# power.net
KiCad netlist of a schematic drawn in Altium Designer
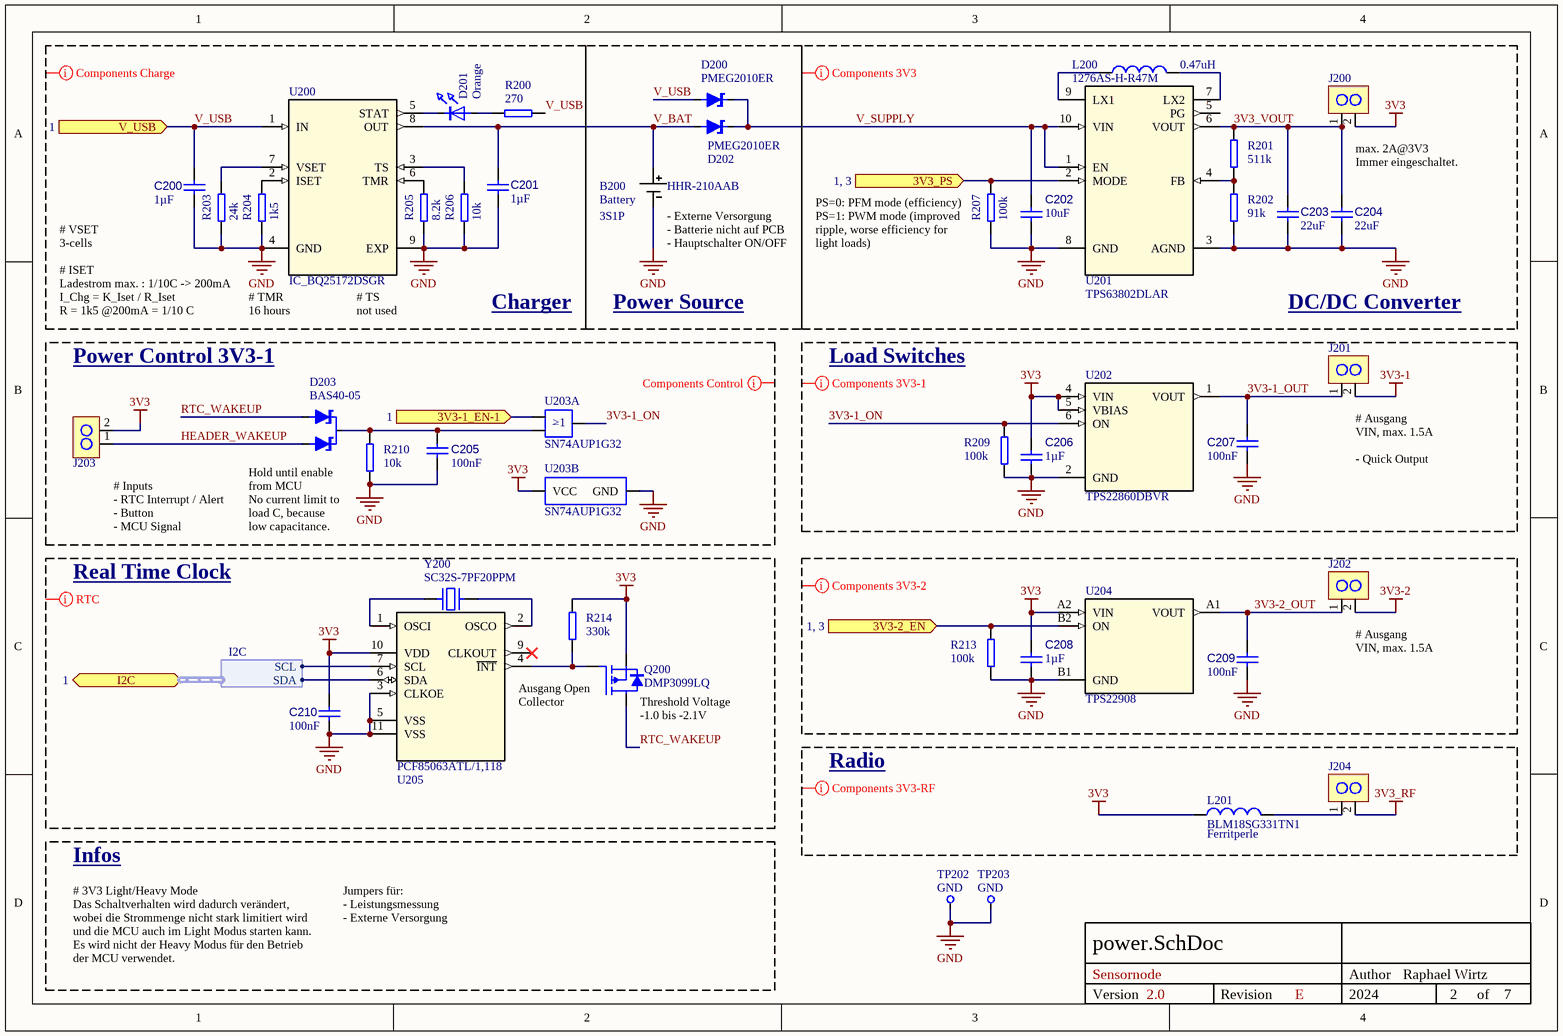
[diagram p0: power.SchDoc]

(export (version "E")
  (design (tool "Eeschema 10.0.6"))
  (components
    (comp (ref "B200")
      (value "Battery")
      (footprint "sensornode:JST-S2B-PH-K-S_V - Cloned")
      (fields (field (name "BATTERY_CONFIG") "3S1P") (field (name "PRODUCT") "HHR-210AAB"))
      (libsource (lib "sensornode_v2") (part "Battery"))
    )
    (comp (ref "C200")
      (value "1µF")
      (footprint "0402")
      (fields
        (field (name "TOLERANCE") "10%")
        (field (name "MANUFACTURER") "TDK")
        (field (name "MANUFACTURER PART NUMBER") "C1005X6S0J105K050BC")
      )
      (libsource (lib "sensornode_v2") (part "C"))
    )
    (comp (ref "C201")
      (value "1µF")
      (footprint "0402")
      (fields
        (field (name "TOLERANCE") "10%")
        (field (name "MANUFACTURER") "TDK")
        (field (name "MANUFACTURER PART NUMBER") "C1005X6S0J105K050BC")
      )
      (libsource (lib "sensornode_v2") (part "C"))
    )
    (comp (ref "C202")
      (value "10uF")
      (footprint "sensornode:0603")
      (fields
        (field (name "TOLERANCE") "10%")
        (field (name "MANUFACTURER") "TDK")
        (field (name "MANUFACTURER PART NUMBER") "C1005X6S0J105K050BC")
      )
      (libsource (lib "sensornode_v2") (part "C"))
    )
    (comp (ref "C203")
      (value "22uF")
      (footprint "sensornode:0603")
      (fields
        (field (name "TOLERANCE") "10%")
        (field (name "MANUFACTURER") "TDK")
        (field (name "MANUFACTURER PART NUMBER") "C1005X6S0J105K050BC")
      )
      (libsource (lib "sensornode_v2") (part "C"))
    )
    (comp (ref "C204")
      (value "22uF")
      (footprint "sensornode:0603")
      (fields
        (field (name "TOLERANCE") "10%")
        (field (name "MANUFACTURER") "TDK")
        (field (name "MANUFACTURER PART NUMBER") "C1005X6S0J105K050BC")
      )
      (libsource (lib "sensornode_v2") (part "C"))
    )
    (comp (ref "C205")
      (value "100nF")
      (footprint "sensornode:0603")
      (fields
        (field (name "TOLERANCE") "10%")
        (field (name "MANUFACTURER") "TDK")
        (field (name "MANUFACTURER PART NUMBER") "C1005X6S0J105K050BC")
      )
      (libsource (lib "sensornode_v2") (part "C"))
    )
    (comp (ref "C206")
      (value "1µF")
      (footprint "sensornode:0603")
      (fields
        (field (name "TOLERANCE") "10%")
        (field (name "MANUFACTURER") "TDK")
        (field (name "MANUFACTURER PART NUMBER") "C1005X6S0J105K050BC")
      )
      (libsource (lib "sensornode_v2") (part "C"))
    )
    (comp (ref "C207")
      (value "100nF")
      (footprint "sensornode:0603")
      (fields
        (field (name "TOLERANCE") "10%")
        (field (name "MANUFACTURER") "TDK")
        (field (name "MANUFACTURER PART NUMBER") "C1005X6S0J105K050BC")
      )
      (libsource (lib "sensornode_v2") (part "C"))
    )
    (comp (ref "C208")
      (value "1µF")
      (footprint "sensornode:0603")
      (fields
        (field (name "TOLERANCE") "10%")
        (field (name "MANUFACTURER") "TDK")
        (field (name "MANUFACTURER PART NUMBER") "C1005X6S0J105K050BC")
      )
      (libsource (lib "sensornode_v2") (part "C"))
    )
    (comp (ref "C209")
      (value "100nF")
      (footprint "sensornode:0603")
      (fields
        (field (name "TOLERANCE") "10%")
        (field (name "MANUFACTURER") "TDK")
        (field (name "MANUFACTURER PART NUMBER") "C1005X6S0J105K050BC")
      )
      (libsource (lib "sensornode_v2") (part "C"))
    )
    (comp (ref "C210")
      (value "100nF")
      (footprint "0402")
      (fields
        (field (name "TOLERANCE") "10%")
        (field (name "MANUFACTURER") "TDK")
        (field (name "MANUFACTURER PART NUMBER") "C1005X6S0J105K050BC")
      )
      (libsource (lib "sensornode_v2") (part "C"))
    )
    (comp (ref "D200")
      (value "PMEG2010ER")
      (footprint "sensornode:SODFL3517X110N")
      (libsource (lib "sensornode_v2") (part "Schotky_1"))
    )
    (comp (ref "D201")
      (value "Orange")
      (footprint "sensornode:0603-Diode")
      (libsource (lib "sensornode_v2") (part "LED_1"))
    )
    (comp (ref "D202")
      (value "PMEG2010ER")
      (footprint "sensornode:SODFL3517X110N")
      (libsource (lib "sensornode_v2") (part "Schotky_1"))
    )
    (comp (ref "D203")
      (value "BAS40-05")
      (footprint "sensornode:SOT-23")
      (libsource (lib "sensornode_v2") (part "Schotky_BAS40-5"))
    )
    (comp (ref "J200")
      (value "HEADER_2x1_TD")
      (footprint "sensornode:HEADER_2_RM_2.54")
      (libsource (lib "sensornode_v2") (part "HEADER_2x1_TD"))
    )
    (comp (ref "J201")
      (value "HEADER_2x1_TD")
      (footprint "sensornode:HEADER_2_RM_2.54")
      (libsource (lib "sensornode_v2") (part "HEADER_2x1_TD"))
    )
    (comp (ref "J202")
      (value "HEADER_2x1_TD")
      (footprint "sensornode:HEADER_2_RM_2.54")
      (libsource (lib "sensornode_v2") (part "HEADER_2x1_TD"))
    )
    (comp (ref "J203")
      (value "HEADER_2x1_TD")
      (footprint "sensornode:HEADER_2_RM_2.54")
      (libsource (lib "") (part "HEADER_2x1_TD_1"))
    )
    (comp (ref "J204")
      (value "HEADER_2x1_TD")
      (footprint "sensornode:HEADER_2_RM_2.54")
      (libsource (lib "sensornode_v2") (part "HEADER_2x1_TD"))
    )
    (comp (ref "L200")
      (value "0.47uH")
      (footprint "sensornode:FP-XFL4015-MFG")
      (fields (field (name "NAME") "1276AS-H-R47M"))
      (libsource (lib "sensornode_v2") (part "L?"))
    )
    (comp (ref "L201")
      (value "BLM18SG331TN1")
      (footprint "sensornode:1608X65N_BEADC")
      (description "330 Ohms @ 100 MHz 1 Power Line Ferrite Bead 0603 (1608 Metric) 1.5A 70mOhm")
      (fields (field (name "INFO") "Ferritperle"))
      (libsource (lib "sensornode_v2") (part "L?"))
    )
    (comp (ref "Q200")
      (value "DMP3099LQ")
      (footprint "SOT-23 - FET")
      (libsource (lib "AMZ_Altium_Lib") (part "MOSFET P"))
    )
    (comp (ref "R200")
      (value "270")
      (footprint "sensornode:0603")
      (description "Normaler Widerstand")
      (libsource (lib "sensornode_v2") (part "R?"))
    )
    (comp (ref "R201")
      (value "511k")
      (footprint "sensornode:0603")
      (description "Normaler Widerstand")
      (libsource (lib "sensornode_v2") (part "R?"))
    )
    (comp (ref "R202")
      (value "91k")
      (footprint "sensornode:0603")
      (description "Normaler Widerstand")
      (libsource (lib "sensornode_v2") (part "R?"))
    )
    (comp (ref "R203")
      (value "24k")
      (footprint "sensornode:0603")
      (description "Normaler Widerstand")
      (libsource (lib "sensornode_v2") (part "R?"))
    )
    (comp (ref "R204")
      (value "1k5")
      (footprint "sensornode:0603")
      (description "Normaler Widerstand")
      (libsource (lib "sensornode_v2") (part "R?"))
    )
    (comp (ref "R205")
      (value "8.2k")
      (footprint "sensornode:0603")
      (description "Normaler Widerstand")
      (libsource (lib "sensornode_v2") (part "R?"))
    )
    (comp (ref "R206")
      (value "10k")
      (footprint "sensornode:0603")
      (description "Normaler Widerstand")
      (libsource (lib "sensornode_v2") (part "R?"))
    )
    (comp (ref "R207")
      (value "100k")
      (footprint "sensornode:0603")
      (description "Normaler Widerstand")
      (libsource (lib "sensornode_v2") (part "R?"))
    )
    (comp (ref "R209")
      (value "100k")
      (footprint "sensornode:0603")
      (description "Normaler Widerstand")
      (libsource (lib "sensornode_v2") (part "R?"))
    )
    (comp (ref "R210")
      (value "10k")
      (footprint "sensornode:0603")
      (description "Normaler Widerstand")
      (libsource (lib "sensornode_v2") (part "R?"))
    )
    (comp (ref "R213")
      (value "100k")
      (footprint "sensornode:0603")
      (description "Normaler Widerstand")
      (libsource (lib "sensornode_v2") (part "R?"))
    )
    (comp (ref "R214")
      (value "330k")
      (footprint "sensornode:0603")
      (description "Normaler Widerstand")
      (libsource (lib "sensornode_v2") (part "R?"))
    )
    (comp (ref "TP202")
      (value "TP_SMD")
      (footprint "sensornode:TP+245X165")
      (description "Testpoint")
      (fields (field (name "NAME") "GND"))
      (libsource (lib "sensornode_v2") (part "Testpoint"))
    )
    (comp (ref "TP203")
      (value "TP_SMD")
      (footprint "sensornode:TP+245X165")
      (description "Testpoint")
      (fields (field (name "NAME") "GND"))
      (libsource (lib "sensornode_v2") (part "Testpoint"))
    )
    (comp (ref "U200")
      (value "IC_BQ25172DSGR")
      (footprint "sensornode:IC_BQ25172DSGR")
      (description "Charge IC. 0.8-A, one- to six-cell NiMH stand-alone linear charger in a QFN package")
      (fields (field (name "MF") "Texas Instruments") (field (name "MP") "BQ25172DSGR"))
      (libsource (lib "sensornode_v2") (part "IC_BQ25172DSGR"))
    )
    (comp (ref "U201")
      (value "TPS63802DLAR")
      (footprint "sensornode:VREG_TPS63802DLAR")
      (fields (field (name "MF") "Richtek USA") (field (name "MP") "RT6150B-33GQW"))
      (libsource (lib "sensornode_v2") (part "TPS63802DLAR"))
    )
    (comp (ref "U202")
      (value "TPS22860DBVR")
      (footprint "sensornode:SOT95P280X145-6N")
      (description "0.73-?, 5-V, ultra-low leakage load switch 6-SOT-23 -40 to 85")
      (fields (field (name "MF") "Texas Instruments") (field (name "DIGI-KEY_PART_NUMBER") "296-43982-1-ND"))
      (libsource (lib "sensornode_v2") (part "TPS22860DBVR"))
    )
    (comp (ref "U203")
      (value "SN74AUP1G32")
      (footprint "sensornode:SOT23-5")
      (libsource (lib "sensornode_v2") (part "Gatter OR1x2_1 SN74AUP1G32"))
    )
    (comp (ref "U204")
      (value "TPS22908")
      (footprint "sensornode:BGA4C50P2X2_88X88X62N")
      (description "3.6-V, 1-A, 28-mΩ On-Resistance Load Switch with Controlled Rise Time")
      (fields (field (name "MP") "TPS22860DBVR") (field (name "MF") "Texas Instruments"))
      (libsource (lib "sensornode_v2") (part "TPS22908"))
    )
    (comp (ref "U205")
      (value "PCF85063ATL/1,118")
      (footprint "sensornode:10-DFN(2.6X2.6)")
      (description "Real Time Clock (RTC) IC Clock/Calendar - IÂ²C, 2-Wire Serial 10-XFDFN Exposed Pad")
      (fields (field (name "MF") "NXP USA"))
      (libsource (lib "sensornode_v2") (part "PCF85063ATL/1,118"))
    )
    (comp (ref "Y200")
      (value "SC32S-7PF20PPM")
      (footprint "sensornode:SC32S7PF20PPM")
      (description "Crystal")
      (libsource (lib "sensornode_v2") (part "Crystal_1"))
    )
  )
  (nets
    (net (code "2") (name "/3V3-1_EN-1") (class "Default")
      (node (ref "U203") (pin "1") (pinfunction "A_1") (pintype "passive"))
    )
    (net (code "3") (name "/3V3-1_ON") (class "Default")
      (node (ref "R209") (pin "1") (pintype "passive"))
      (node (ref "U202") (pin "6") (pinfunction "ON_6") (pintype "input"))
      (node (ref "U203") (pin "4") (pinfunction "Y_4") (pintype "passive"))
    )
    (net (code "4") (name "/3V3-1_OUT") (class "Default")
      (node (ref "C207") (pin "2") (pinfunction "2_2") (pintype "passive"))
      (node (ref "J201") (pin "1") (pinfunction "1_1") (pintype "passive"))
      (node (ref "U202") (pin "1") (pinfunction "VOUT_1") (pintype "output"))
    )
    (net (code "5") (name "/3V3-2_EN") (class "Default")
      (node (ref "R213") (pin "1") (pintype "passive"))
      (node (ref "U204") (pin "B2") (pinfunction "ON_B2") (pintype "input"))
    )
    (net (code "6") (name "/3V3-2_OUT") (class "Default")
      (node (ref "C209") (pin "2") (pinfunction "2_2") (pintype "passive"))
      (node (ref "J202") (pin "1") (pinfunction "1_1") (pintype "passive"))
      (node (ref "U204") (pin "A1") (pinfunction "VOUT_A1") (pintype "output"))
    )
    (net (code "7") (name "/3V3_PS") (class "Default")
      (node (ref "R207") (pin "2") (pintype "passive"))
      (node (ref "U201") (pin "2") (pinfunction "MODE_2") (pintype "input"))
    )
    (net (code "8") (name "/3V3_VOUT") (class "Default")
      (node (ref "C203") (pin "2") (pinfunction "2_2") (pintype "passive"))
      (node (ref "C204") (pin "2") (pinfunction "2_2") (pintype "passive"))
      (node (ref "J200") (pin "1") (pinfunction "1_1") (pintype "passive"))
      (node (ref "R201") (pin "1") (pintype "passive"))
      (node (ref "U201") (pin "6") (pinfunction "VOUT_6") (pintype "output"))
    )
    (net (code "9") (name "/HEADER_WAKEUP") (class "Default")
      (node (ref "D203") (pin "2") (pinfunction "A_2") (pintype "passive"))
      (node (ref "J203") (pin "1") (pinfunction "1_1") (pintype "passive"))
    )
    (net (code "10") (name "/RTC_WAKEUP") (class "Default")
      (node (ref "D203") (pin "1") (pinfunction "A_1") (pintype "passive"))
      (node (ref "Q200") (pin "D") (pinfunction "DRAIN_D") (pintype "passive"))
    )
    (net (code "11") (name "/SCL") (class "Default")
      (node (ref "U205") (pin "7") (pinfunction "SCL_7") (pintype "input"))
    )
    (net (code "12") (name "/SDA") (class "Default")
      (node (ref "U205") (pin "6") (pinfunction "SDA_6") (pintype "bidirectional"))
    )
    (net (code "13") (name "/V_BAT") (class "Default")
      (node (ref "B200") (pin "1") (pinfunction "+_1") (pintype "passive"))
      (node (ref "C201") (pin "2") (pinfunction "2_2") (pintype "passive"))
      (node (ref "D202") (pin "A") (pinfunction "A_A") (pintype "passive"))
      (node (ref "U200") (pin "8") (pinfunction "OUT_8") (pintype "output"))
    )
    (net (code "14") (name "/V_SUPPLY") (class "Default")
      (node (ref "C202") (pin "2") (pinfunction "2_2") (pintype "passive"))
      (node (ref "D200") (pin "K") (pinfunction "K_K") (pintype "passive"))
      (node (ref "D202") (pin "K") (pinfunction "K_K") (pintype "passive"))
      (node (ref "U201") (pin "1") (pinfunction "EN_1") (pintype "input"))
      (node (ref "U201") (pin "10") (pinfunction "VIN_10") (pintype "input"))
    )
    (net (code "15") (name "/V_USB") (class "Default")
      (node (ref "C200") (pin "2") (pinfunction "2_2") (pintype "passive"))
      (node (ref "D200") (pin "A") (pinfunction "A_A") (pintype "passive"))
      (node (ref "R200") (pin "2") (pintype "passive"))
      (node (ref "U200") (pin "1") (pinfunction "IN_1") (pintype "input"))
    )
    (net (code "17") (name "3V3") (class "Default")
      (node (ref "C206") (pin "2") (pinfunction "2_2") (pintype "passive"))
      (node (ref "C208") (pin "2") (pinfunction "2_2") (pintype "passive"))
      (node (ref "C210") (pin "2") (pinfunction "2_2") (pintype "passive"))
      (node (ref "J200") (pin "2") (pinfunction "2_2") (pintype "passive"))
      (node (ref "J203") (pin "2") (pinfunction "2_2") (pintype "passive"))
      (node (ref "L201") (pin "1") (pinfunction "1_1") (pintype "passive"))
      (node (ref "Q200") (pin "S") (pinfunction "SOURCE_S") (pintype "passive"))
      (node (ref "R214") (pin "2") (pintype "passive"))
      (node (ref "U202") (pin "4") (pinfunction "VIN_4") (pintype "input"))
      (node (ref "U202") (pin "5") (pinfunction "VBIAS_5") (pintype "input"))
      (node (ref "U203") (pin "5") (pinfunction "VCC_5") (pintype "passive"))
      (node (ref "U204") (pin "A2") (pinfunction "VIN_A2") (pintype "input"))
      (node (ref "U205") (pin "10") (pinfunction "VDD_10") (pintype "power_in"))
    )
    (net (code "18") (name "3V3-1") (class "Default")
      (node (ref "J201") (pin "2") (pinfunction "2_2") (pintype "passive"))
    )
    (net (code "19") (name "3V3-2") (class "Default")
      (node (ref "J202") (pin "2") (pinfunction "2_2") (pintype "passive"))
    )
    (net (code "20") (name "3V3_RF") (class "Default")
      (node (ref "J204") (pin "2") (pinfunction "2_2") (pintype "passive"))
    )
    (net (code "21") (name "GND") (class "Default")
      (node (ref "B200") (pin "2") (pinfunction "-_2") (pintype "passive"))
      (node (ref "C200") (pin "1") (pinfunction "1_1") (pintype "passive"))
      (node (ref "C201") (pin "1") (pinfunction "1_1") (pintype "passive"))
      (node (ref "C202") (pin "1") (pinfunction "1_1") (pintype "passive"))
      (node (ref "C203") (pin "1") (pinfunction "1_1") (pintype "passive"))
      (node (ref "C204") (pin "1") (pinfunction "1_1") (pintype "passive"))
      (node (ref "C205") (pin "1") (pinfunction "1_1") (pintype "passive"))
      (node (ref "C206") (pin "1") (pinfunction "1_1") (pintype "passive"))
      (node (ref "C207") (pin "1") (pinfunction "1_1") (pintype "passive"))
      (node (ref "C208") (pin "1") (pinfunction "1_1") (pintype "passive"))
      (node (ref "C209") (pin "1") (pinfunction "1_1") (pintype "passive"))
      (node (ref "C210") (pin "1") (pinfunction "1_1") (pintype "passive"))
      (node (ref "R202") (pin "2") (pintype "passive"))
      (node (ref "R203") (pin "2") (pintype "passive"))
      (node (ref "R204") (pin "2") (pintype "passive"))
      (node (ref "R205") (pin "2") (pintype "passive"))
      (node (ref "R206") (pin "2") (pintype "passive"))
      (node (ref "R207") (pin "1") (pintype "passive"))
      (node (ref "R209") (pin "2") (pintype "passive"))
      (node (ref "R210") (pin "1") (pintype "passive"))
      (node (ref "R213") (pin "2") (pintype "passive"))
      (node (ref "TP202") (pin "1") (pinfunction "1_1") (pintype "passive"))
      (node (ref "TP203") (pin "1") (pinfunction "1_1") (pintype "passive"))
      (node (ref "U200") (pin "4") (pinfunction "GND_4") (pintype "power_in"))
      (node (ref "U200") (pin "9") (pinfunction "EXP_9") (pintype "power_in"))
      (node (ref "U201") (pin "3") (pinfunction "AGND_3") (pintype "power_in"))
      (node (ref "U201") (pin "8") (pinfunction "GND_8") (pintype "power_in"))
      (node (ref "U202") (pin "2") (pinfunction "GND_2") (pintype "power_in"))
      (node (ref "U203") (pin "3") (pinfunction "GND_3") (pintype "passive"))
      (node (ref "U204") (pin "B1") (pinfunction "GND_B1") (pintype "power_in"))
      (node (ref "U205") (pin "11") (pinfunction "VSS_11") (pintype "power_in"))
      (node (ref "U205") (pin "3") (pinfunction "CLKOE_3") (pintype "input"))
      (node (ref "U205") (pin "5") (pinfunction "VSS_5") (pintype "power_in"))
    )
    (net (code "22") (name "Net-(D201-PadA)") (class "Default")
      (node (ref "D201") (pin "A") (pinfunction "A_A") (pintype "passive"))
      (node (ref "R200") (pin "1") (pintype "passive"))
    )
    (net (code "23") (name "Net-(D203-K)") (class "Default")
      (node (ref "C205") (pin "2") (pinfunction "2_2") (pintype "passive"))
      (node (ref "D203") (pin "3") (pinfunction "K_3") (pintype "passive"))
      (node (ref "R210") (pin "2") (pintype "passive"))
      (node (ref "U203") (pin "2") (pinfunction "B_2") (pintype "passive"))
    )
    (net (code "24") (name "Net-(J204-Pad1)") (class "Default")
      (node (ref "J204") (pin "1") (pinfunction "1_1") (pintype "passive"))
      (node (ref "L201") (pin "2") (pinfunction "2_2") (pintype "passive"))
    )
    (net (code "25") (name "Net-(Q200-GATE)") (class "Default")
      (node (ref "Q200") (pin "G") (pinfunction "GATE_G") (pintype "passive"))
      (node (ref "R214") (pin "1") (pintype "passive"))
      (node (ref "U205") (pin "4") (pinfunction "~{INT}_4") (pintype "output"))
    )
    (net (code "26") (name "Net-(U200-ISET)") (class "Default")
      (node (ref "R204") (pin "1") (pintype "passive"))
      (node (ref "U200") (pin "2") (pinfunction "ISET_2") (pintype "input"))
    )
    (net (code "27") (name "Net-(U200-STAT)") (class "Default")
      (node (ref "D201") (pin "K") (pinfunction "K_K") (pintype "passive"))
      (node (ref "U200") (pin "5") (pinfunction "STAT_5") (pintype "output"))
    )
    (net (code "28") (name "Net-(U200-TMR)") (class "Default")
      (node (ref "R205") (pin "1") (pintype "passive"))
      (node (ref "U200") (pin "6") (pinfunction "TMR_6") (pintype "input"))
    )
    (net (code "29") (name "Net-(U200-TS)") (class "Default")
      (node (ref "R206") (pin "1") (pintype "passive"))
      (node (ref "U200") (pin "3") (pinfunction "TS_3") (pintype "input"))
    )
    (net (code "30") (name "Net-(U200-VSET)") (class "Default")
      (node (ref "R203") (pin "1") (pintype "passive"))
      (node (ref "U200") (pin "7") (pinfunction "VSET_7") (pintype "input"))
    )
    (net (code "31") (name "Net-(U201-FB)") (class "Default")
      (node (ref "R201") (pin "2") (pintype "passive"))
      (node (ref "R202") (pin "1") (pintype "passive"))
      (node (ref "U201") (pin "4") (pinfunction "FB_4") (pintype "input"))
    )
    (net (code "32") (name "Net-(U201-LX1)") (class "Default")
      (node (ref "L200") (pin "1") (pinfunction "1_1") (pintype "passive"))
      (node (ref "U201") (pin "9") (pinfunction "LX1_9") (pintype "passive"))
    )
    (net (code "33") (name "Net-(U201-LX2)") (class "Default")
      (node (ref "L200") (pin "2") (pinfunction "2_2") (pintype "passive"))
      (node (ref "U201") (pin "7") (pinfunction "LX2_7") (pintype "passive"))
    )
    (net (code "34") (name "Net-(U205-OSCI)") (class "Default")
      (node (ref "U205") (pin "1") (pinfunction "OSCI_1") (pintype "input"))
      (node (ref "Y200") (pin "1") (pinfunction "1_1") (pintype "passive"))
    )
    (net (code "35") (name "Net-(U205-OSCO)") (class "Default")
      (node (ref "U205") (pin "2") (pinfunction "OSCO_2") (pintype "output"))
      (node (ref "Y200") (pin "2") (pinfunction "2_2") (pintype "passive"))
    )
    (net (code "36") (name "unconnected-(U201-PG-Pad5)") (class "Default")
      (node (ref "U201") (pin "5") (pinfunction "PG_5") (pintype "output"))
    )
    (net (code "37") (name "unconnected-(U205-CLKOUT-Pad9)") (class "Default")
      (node (ref "U205") (pin "9") (pinfunction "CLKOUT_9") (pintype "output+no_connect"))
    )
  )
)
